# TopPanelV3_1.net
KiCad netlist of a schematic drawn in EAGLE
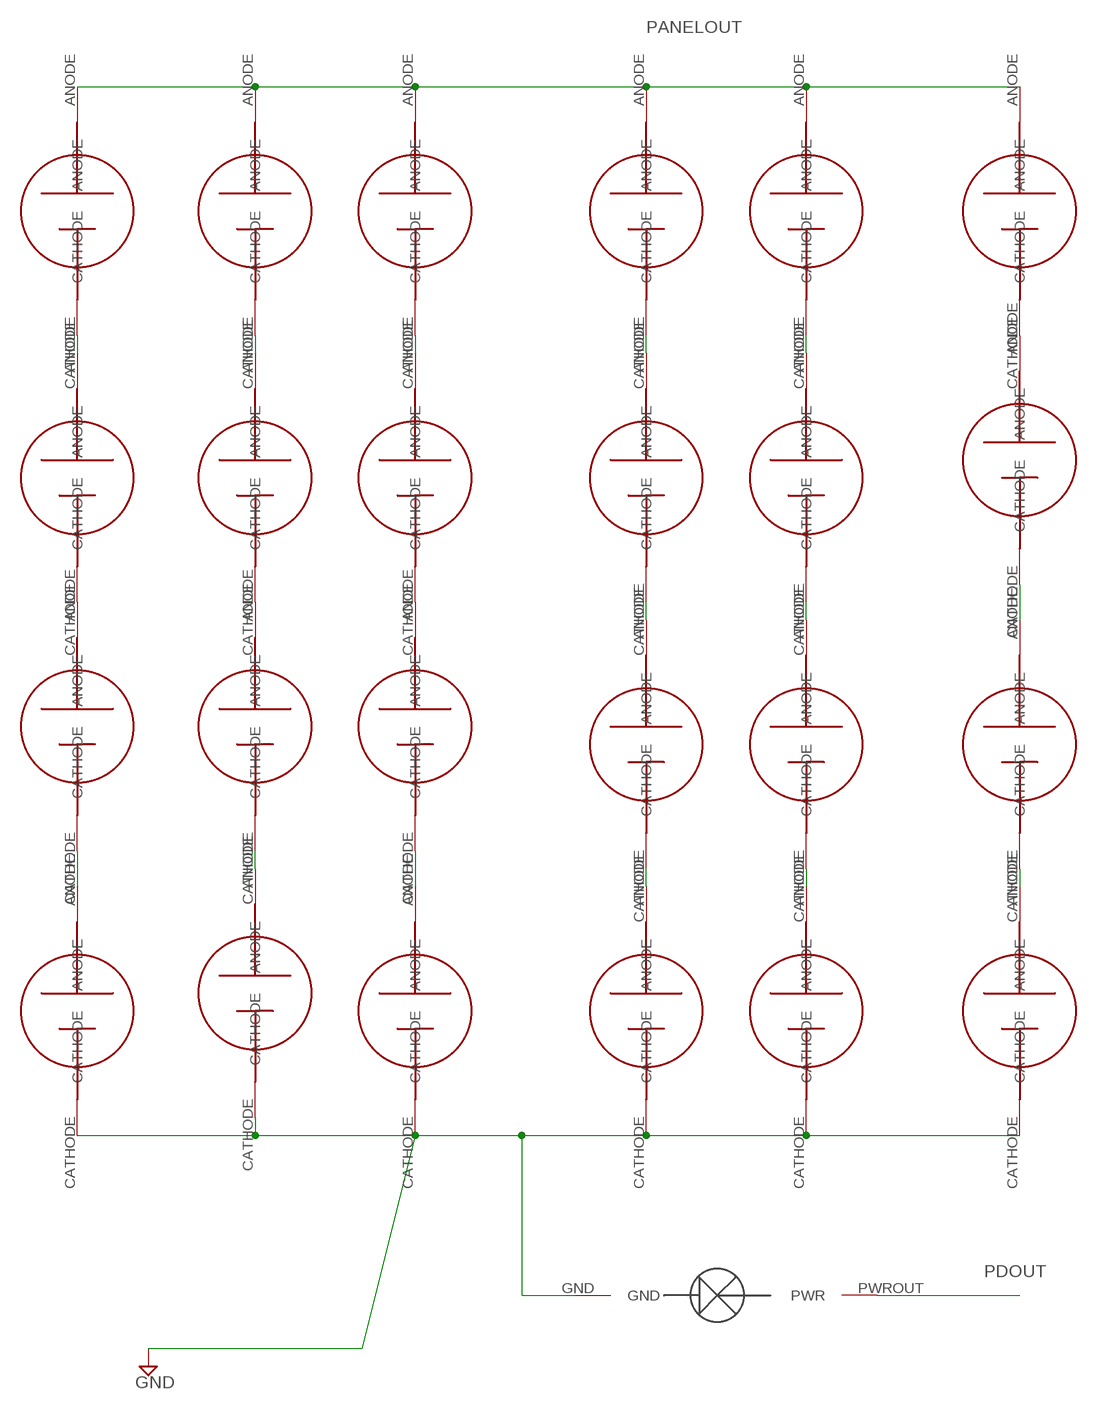
[diagram p0: schematic, sheet 1]

(export (version "E")
  (design (tool "Eeschema 10.0.6"))
  (components
    (comp (ref "1A")
      (value "SOLARCELL")
      (footprint "eagle-import:SOLARCELL")
      (libsource (lib "eagle-import") (part "SOLARCELL"))
    )
    (comp (ref "1B")
      (value "SOLARCELL")
      (footprint "eagle-import:SOLARCELL")
      (libsource (lib "eagle-import") (part "SOLARCELL"))
    )
    (comp (ref "1C")
      (value "SOLARCELL")
      (footprint "eagle-import:SOLARCELL")
      (libsource (lib "eagle-import") (part "SOLARCELL"))
    )
    (comp (ref "1D")
      (value "SOLARCELL")
      (footprint "eagle-import:SOLARCELL")
      (libsource (lib "eagle-import") (part "SOLARCELL"))
    )
    (comp (ref "2A")
      (value "SOLARCELL")
      (footprint "eagle-import:SOLARCELL")
      (libsource (lib "eagle-import") (part "SOLARCELL"))
    )
    (comp (ref "2B")
      (value "SOLARCELL")
      (footprint "eagle-import:SOLARCELL")
      (libsource (lib "eagle-import") (part "SOLARCELL"))
    )
    (comp (ref "2C")
      (value "SOLARCELL")
      (footprint "eagle-import:SOLARCELL")
      (libsource (lib "eagle-import") (part "SOLARCELL"))
    )
    (comp (ref "2D")
      (value "SOLARCELL")
      (footprint "eagle-import:SOLARCELL")
      (libsource (lib "eagle-import") (part "SOLARCELL"))
    )
    (comp (ref "3A")
      (value "SOLARCELL")
      (footprint "eagle-import:SOLARCELL")
      (libsource (lib "eagle-import") (part "SOLARCELL"))
    )
    (comp (ref "3B")
      (value "SOLARCELL")
      (footprint "eagle-import:SOLARCELL")
      (libsource (lib "eagle-import") (part "SOLARCELL"))
    )
    (comp (ref "3C")
      (value "SOLARCELL")
      (footprint "eagle-import:SOLARCELL")
      (libsource (lib "eagle-import") (part "SOLARCELL"))
    )
    (comp (ref "3D")
      (value "SOLARCELL")
      (footprint "eagle-import:SOLARCELL")
      (libsource (lib "eagle-import") (part "SOLARCELL"))
    )
    (comp (ref "4A")
      (value "SOLARCELL")
      (footprint "eagle-import:SOLARCELL")
      (libsource (lib "eagle-import") (part "SOLARCELL"))
    )
    (comp (ref "4B")
      (value "SOLARCELL")
      (footprint "eagle-import:SOLARCELL")
      (libsource (lib "eagle-import") (part "SOLARCELL"))
    )
    (comp (ref "4C")
      (value "SOLARCELL")
      (footprint "eagle-import:SOLARCELL")
      (libsource (lib "eagle-import") (part "SOLARCELL"))
    )
    (comp (ref "4D")
      (value "SOLARCELL")
      (footprint "eagle-import:SOLARCELL")
      (libsource (lib "eagle-import") (part "SOLARCELL"))
    )
    (comp (ref "5A")
      (value "SOLARCELL")
      (footprint "eagle-import:SOLARCELL")
      (libsource (lib "eagle-import") (part "SOLARCELL"))
    )
    (comp (ref "5B")
      (value "SOLARCELL")
      (footprint "eagle-import:SOLARCELL")
      (libsource (lib "eagle-import") (part "SOLARCELL"))
    )
    (comp (ref "5C")
      (value "SOLARCELL")
      (footprint "eagle-import:SOLARCELL")
      (libsource (lib "eagle-import") (part "SOLARCELL"))
    )
    (comp (ref "5D")
      (value "SOLARCELL")
      (footprint "eagle-import:SOLARCELL")
      (libsource (lib "eagle-import") (part "SOLARCELL"))
    )
    (comp (ref "6A")
      (value "SOLARCELL")
      (footprint "eagle-import:SOLARCELL")
      (libsource (lib "eagle-import") (part "SOLARCELL"))
    )
    (comp (ref "6B")
      (value "SOLARCELL")
      (footprint "eagle-import:SOLARCELL")
      (libsource (lib "eagle-import") (part "SOLARCELL"))
    )
    (comp (ref "6C")
      (value "SOLARCELL")
      (footprint "eagle-import:SOLARCELL")
      (libsource (lib "eagle-import") (part "SOLARCELL"))
    )
    (comp (ref "6D")
      (value "SOLARCELL")
      (footprint "eagle-import:SOLARCELL")
      (libsource (lib "eagle-import") (part "SOLARCELL"))
    )
    (comp (ref "U$1")
      (value "PHOTODETECTOR")
      (footprint "eagle-import:PHOTODECTORDEVICE2")
      (libsource (lib "eagle-import") (part "PHOTODETECTOR"))
    )
  )
  (nets
    (net (code "1") (name "/PANELOUT") (class "Default")
      (node (ref "1A") (pin "ANODE") (pinfunction "ANODE_ANODE") (pintype "bidirectional"))
      (node (ref "2A") (pin "ANODE") (pinfunction "ANODE_ANODE") (pintype "bidirectional"))
      (node (ref "3A") (pin "ANODE") (pinfunction "ANODE_ANODE") (pintype "bidirectional"))
      (node (ref "4A") (pin "ANODE") (pinfunction "ANODE_ANODE") (pintype "bidirectional"))
      (node (ref "5A") (pin "ANODE") (pinfunction "ANODE_ANODE") (pintype "bidirectional"))
      (node (ref "6A") (pin "ANODE") (pinfunction "ANODE_ANODE") (pintype "bidirectional"))
    )
    (net (code "2") (name "/PDOUT") (class "Default")
      (node (ref "U$1") (pin "PWROUT") (pinfunction "PWR_PWROUT") (pintype "bidirectional"))
    )
    (net (code "3") (name "GND") (class "Default")
      (node (ref "1D") (pin "CATHODE") (pinfunction "CATHODE_CATHODE") (pintype "bidirectional"))
      (node (ref "2D") (pin "CATHODE") (pinfunction "CATHODE_CATHODE") (pintype "bidirectional"))
      (node (ref "3D") (pin "CATHODE") (pinfunction "CATHODE_CATHODE") (pintype "bidirectional"))
      (node (ref "4D") (pin "CATHODE") (pinfunction "CATHODE_CATHODE") (pintype "bidirectional"))
      (node (ref "5D") (pin "CATHODE") (pinfunction "CATHODE_CATHODE") (pintype "bidirectional"))
      (node (ref "6D") (pin "CATHODE") (pinfunction "CATHODE_CATHODE") (pintype "bidirectional"))
      (node (ref "U$1") (pin "GND") (pinfunction "GND_GND") (pintype "bidirectional"))
    )
    (net (code "4") (name "Net-(1A-PadCATHODE)") (class "Default")
      (node (ref "1A") (pin "CATHODE") (pinfunction "CATHODE_CATHODE") (pintype "bidirectional"))
      (node (ref "1B") (pin "ANODE") (pinfunction "ANODE_ANODE") (pintype "bidirectional"))
    )
    (net (code "5") (name "Net-(1B-PadCATHODE)") (class "Default")
      (node (ref "1B") (pin "CATHODE") (pinfunction "CATHODE_CATHODE") (pintype "bidirectional"))
      (node (ref "1C") (pin "ANODE") (pinfunction "ANODE_ANODE") (pintype "bidirectional"))
    )
    (net (code "6") (name "Net-(1C-PadCATHODE)") (class "Default")
      (node (ref "1C") (pin "CATHODE") (pinfunction "CATHODE_CATHODE") (pintype "bidirectional"))
      (node (ref "1D") (pin "ANODE") (pinfunction "ANODE_ANODE") (pintype "bidirectional"))
    )
    (net (code "7") (name "Net-(2A-PadCATHODE)") (class "Default")
      (node (ref "2A") (pin "CATHODE") (pinfunction "CATHODE_CATHODE") (pintype "bidirectional"))
      (node (ref "2B") (pin "ANODE") (pinfunction "ANODE_ANODE") (pintype "bidirectional"))
    )
    (net (code "8") (name "Net-(2B-PadCATHODE)") (class "Default")
      (node (ref "2B") (pin "CATHODE") (pinfunction "CATHODE_CATHODE") (pintype "bidirectional"))
      (node (ref "2C") (pin "ANODE") (pinfunction "ANODE_ANODE") (pintype "bidirectional"))
    )
    (net (code "9") (name "Net-(2C-PadCATHODE)") (class "Default")
      (node (ref "2C") (pin "CATHODE") (pinfunction "CATHODE_CATHODE") (pintype "bidirectional"))
      (node (ref "2D") (pin "ANODE") (pinfunction "ANODE_ANODE") (pintype "bidirectional"))
    )
    (net (code "10") (name "Net-(3A-PadCATHODE)") (class "Default")
      (node (ref "3A") (pin "CATHODE") (pinfunction "CATHODE_CATHODE") (pintype "bidirectional"))
      (node (ref "3B") (pin "ANODE") (pinfunction "ANODE_ANODE") (pintype "bidirectional"))
    )
    (net (code "11") (name "Net-(3B-PadCATHODE)") (class "Default")
      (node (ref "3B") (pin "CATHODE") (pinfunction "CATHODE_CATHODE") (pintype "bidirectional"))
      (node (ref "3C") (pin "ANODE") (pinfunction "ANODE_ANODE") (pintype "bidirectional"))
    )
    (net (code "12") (name "Net-(3C-PadCATHODE)") (class "Default")
      (node (ref "3C") (pin "CATHODE") (pinfunction "CATHODE_CATHODE") (pintype "bidirectional"))
      (node (ref "3D") (pin "ANODE") (pinfunction "ANODE_ANODE") (pintype "bidirectional"))
    )
    (net (code "13") (name "Net-(4A-PadCATHODE)") (class "Default")
      (node (ref "4A") (pin "CATHODE") (pinfunction "CATHODE_CATHODE") (pintype "bidirectional"))
      (node (ref "4B") (pin "ANODE") (pinfunction "ANODE_ANODE") (pintype "bidirectional"))
    )
    (net (code "14") (name "Net-(4B-PadCATHODE)") (class "Default")
      (node (ref "4B") (pin "CATHODE") (pinfunction "CATHODE_CATHODE") (pintype "bidirectional"))
      (node (ref "4C") (pin "ANODE") (pinfunction "ANODE_ANODE") (pintype "bidirectional"))
    )
    (net (code "15") (name "Net-(4C-PadCATHODE)") (class "Default")
      (node (ref "4C") (pin "CATHODE") (pinfunction "CATHODE_CATHODE") (pintype "bidirectional"))
      (node (ref "4D") (pin "ANODE") (pinfunction "ANODE_ANODE") (pintype "bidirectional"))
    )
    (net (code "16") (name "Net-(5A-PadCATHODE)") (class "Default")
      (node (ref "5A") (pin "CATHODE") (pinfunction "CATHODE_CATHODE") (pintype "bidirectional"))
      (node (ref "5B") (pin "ANODE") (pinfunction "ANODE_ANODE") (pintype "bidirectional"))
    )
    (net (code "17") (name "Net-(5B-PadCATHODE)") (class "Default")
      (node (ref "5B") (pin "CATHODE") (pinfunction "CATHODE_CATHODE") (pintype "bidirectional"))
      (node (ref "5C") (pin "ANODE") (pinfunction "ANODE_ANODE") (pintype "bidirectional"))
    )
    (net (code "18") (name "Net-(5C-PadCATHODE)") (class "Default")
      (node (ref "5C") (pin "CATHODE") (pinfunction "CATHODE_CATHODE") (pintype "bidirectional"))
      (node (ref "5D") (pin "ANODE") (pinfunction "ANODE_ANODE") (pintype "bidirectional"))
    )
    (net (code "19") (name "Net-(6A-PadCATHODE)") (class "Default")
      (node (ref "6A") (pin "CATHODE") (pinfunction "CATHODE_CATHODE") (pintype "bidirectional"))
      (node (ref "6B") (pin "ANODE") (pinfunction "ANODE_ANODE") (pintype "bidirectional"))
    )
    (net (code "20") (name "Net-(6B-PadCATHODE)") (class "Default")
      (node (ref "6B") (pin "CATHODE") (pinfunction "CATHODE_CATHODE") (pintype "bidirectional"))
      (node (ref "6C") (pin "ANODE") (pinfunction "ANODE_ANODE") (pintype "bidirectional"))
    )
    (net (code "21") (name "Net-(6C-PadCATHODE)") (class "Default")
      (node (ref "6C") (pin "CATHODE") (pinfunction "CATHODE_CATHODE") (pintype "bidirectional"))
      (node (ref "6D") (pin "ANODE") (pinfunction "ANODE_ANODE") (pintype "bidirectional"))
    )
  )
)
